# IO.net
KiCad netlist of a schematic drawn in Altium Designer
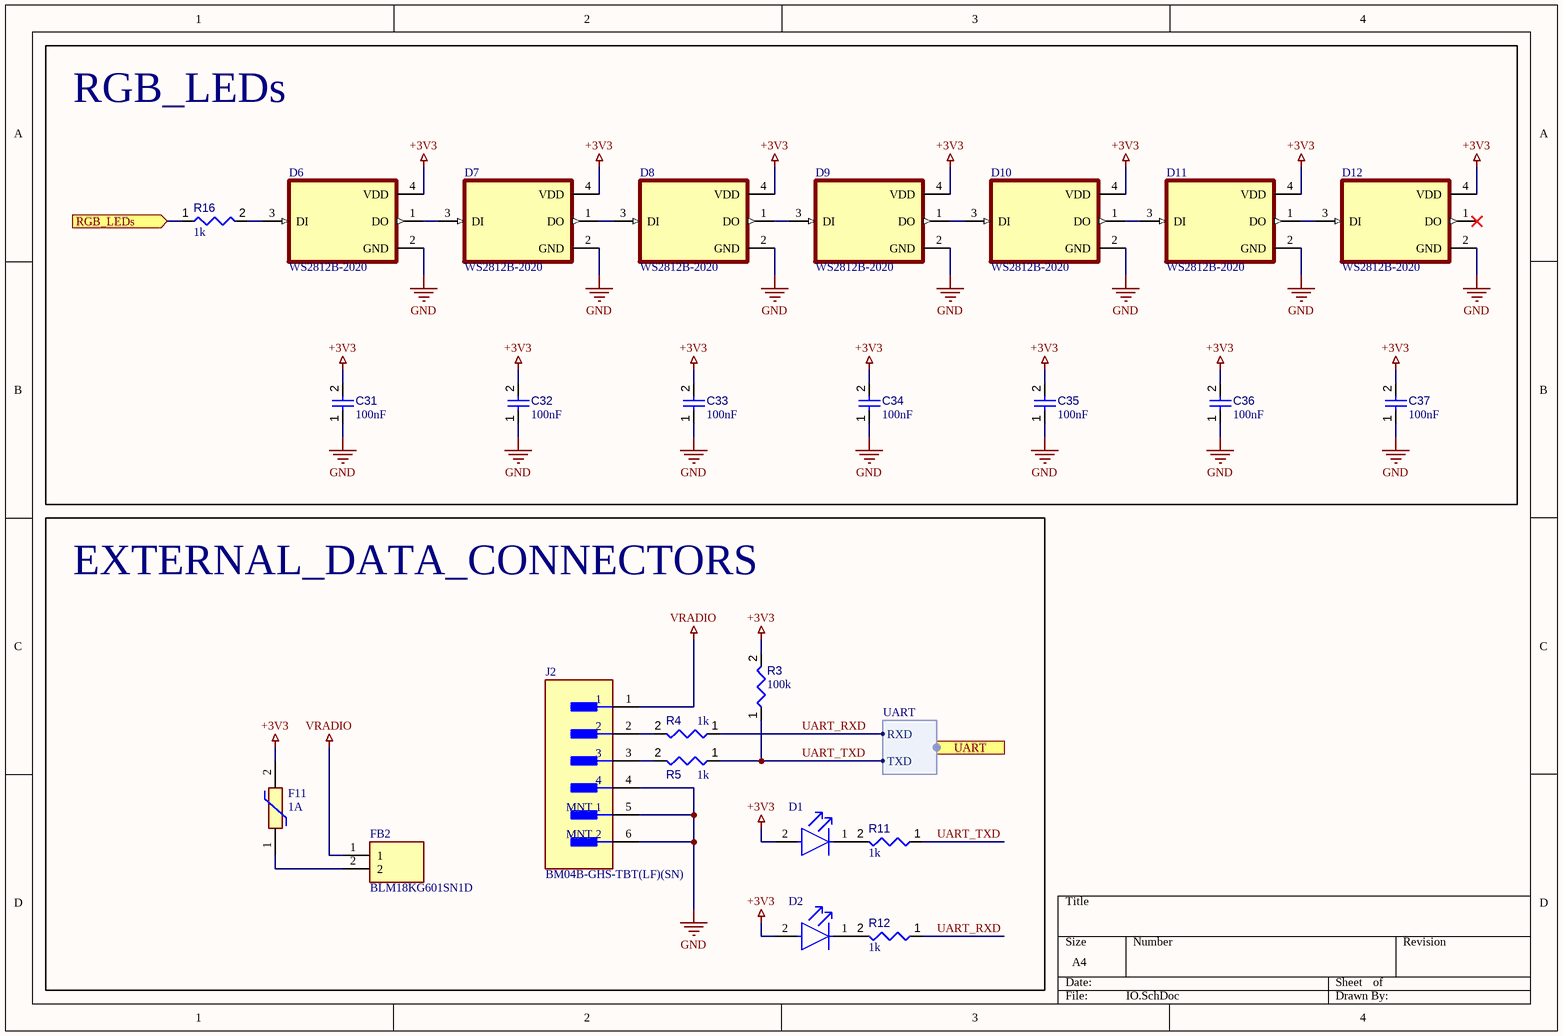
[diagram p0: IO.SchDoc]

(export (version "E")
  (design (tool "Eeschema 10.0.6"))
  (components
    (comp (ref "C31")
      (value "100nF")
      (footprint "CAPC0402(1005)60_L")
      (description "Chip Capacitor, 100nF +/-20%, 10V, 0402, Thickness 0.6 mm")
      (fields (field (name "TOLERANCE") "20%") (field (name "Comment") "Capacitor 100nF +/-20% 10V 0402"))
      (libsource (lib "PWr in Space team") (part "CAP-NP-2"))
    )
    (comp (ref "C32")
      (value "100nF")
      (footprint "CAPC0402(1005)60_L")
      (description "Chip Capacitor, 100nF +/-20%, 10V, 0402, Thickness 0.6 mm")
      (fields (field (name "TOLERANCE") "20%") (field (name "Comment") "Capacitor 100nF +/-20% 10V 0402"))
      (libsource (lib "PWr in Space team") (part "CAP-NP-2"))
    )
    (comp (ref "C33")
      (value "100nF")
      (footprint "CAPC0402(1005)60_L")
      (description "Chip Capacitor, 100nF +/-20%, 10V, 0402, Thickness 0.6 mm")
      (fields (field (name "TOLERANCE") "20%") (field (name "Comment") "Capacitor 100nF +/-20% 10V 0402"))
      (libsource (lib "PWr in Space team") (part "CAP-NP-2"))
    )
    (comp (ref "C34")
      (value "100nF")
      (footprint "CAPC0402(1005)60_L")
      (description "Chip Capacitor, 100nF +/-20%, 10V, 0402, Thickness 0.6 mm")
      (fields (field (name "TOLERANCE") "20%") (field (name "Comment") "Capacitor 100nF +/-20% 10V 0402"))
      (libsource (lib "PWr in Space team") (part "CAP-NP-2"))
    )
    (comp (ref "C35")
      (value "100nF")
      (footprint "CAPC0402(1005)60_L")
      (description "Chip Capacitor, 100nF +/-20%, 10V, 0402, Thickness 0.6 mm")
      (fields (field (name "TOLERANCE") "20%") (field (name "Comment") "Capacitor 100nF +/-20% 10V 0402"))
      (libsource (lib "PWr in Space team") (part "CAP-NP-2"))
    )
    (comp (ref "C36")
      (value "100nF")
      (footprint "CAPC0402(1005)60_L")
      (description "Chip Capacitor, 100nF +/-20%, 10V, 0402, Thickness 0.6 mm")
      (fields (field (name "TOLERANCE") "20%") (field (name "Comment") "Capacitor 100nF +/-20% 10V 0402"))
      (libsource (lib "PWr in Space team") (part "CAP-NP-2"))
    )
    (comp (ref "C37")
      (value "100nF")
      (footprint "CAPC0402(1005)60_L")
      (description "Chip Capacitor, 100nF +/-20%, 10V, 0402, Thickness 0.6 mm")
      (fields (field (name "TOLERANCE") "20%") (field (name "Comment") "Capacitor 100nF +/-20% 10V 0402"))
      (libsource (lib "PWr in Space team") (part "CAP-NP-2"))
    )
    (comp (ref "D1")
      (value "~")
      (footprint "FP-LTST-C191TBKT-MFG")
      (description "LED BLUE CLEAR CHIP SMD")
      (libsource (lib "Altium Content Vault") (part "8706943c75ba83719d021d2fdc84c58"))
    )
    (comp (ref "D2")
      (value "~")
      (footprint "FP-LTST-C191TBKT-MFG")
      (description "LED BLUE CLEAR CHIP SMD")
      (libsource (lib "Altium Content Vault") (part "8706943c75ba83719d021d2fdc84c58"))
    )
    (comp (ref "D6")
      (value "WS2812B-2020")
      (footprint "LED_WS2812-2020")
      (description "Intelligent control LED integrated light source")
      (fields (field (name "MP") "WS2812-2020") (field (name "MF") "{'manufacturer': u'Worldsemi'}"))
      (libsource (lib "SnapEDA_Library") (part "WS2812-2020"))
    )
    (comp (ref "D7")
      (value "WS2812B-2020")
      (footprint "LED_WS2812-2020")
      (description "Intelligent control LED integrated light source")
      (fields (field (name "MP") "WS2812-2020") (field (name "MF") "{'manufacturer': u'Worldsemi'}"))
      (libsource (lib "SnapEDA_Library") (part "WS2812-2020"))
    )
    (comp (ref "D8")
      (value "WS2812B-2020")
      (footprint "LED_WS2812-2020")
      (description "Intelligent control LED integrated light source")
      (fields (field (name "MP") "WS2812-2020") (field (name "MF") "{'manufacturer': u'Worldsemi'}"))
      (libsource (lib "SnapEDA_Library") (part "WS2812-2020"))
    )
    (comp (ref "D9")
      (value "WS2812B-2020")
      (footprint "LED_WS2812-2020")
      (description "Intelligent control LED integrated light source")
      (fields (field (name "MP") "WS2812-2020") (field (name "MF") "{'manufacturer': u'Worldsemi'}"))
      (libsource (lib "SnapEDA_Library") (part "WS2812-2020"))
    )
    (comp (ref "D10")
      (value "WS2812B-2020")
      (footprint "LED_WS2812-2020")
      (description "Intelligent control LED integrated light source")
      (fields (field (name "MP") "WS2812-2020") (field (name "MF") "{'manufacturer': u'Worldsemi'}"))
      (libsource (lib "SnapEDA_Library") (part "WS2812-2020"))
    )
    (comp (ref "D11")
      (value "WS2812B-2020")
      (footprint "LED_WS2812-2020")
      (description "Intelligent control LED integrated light source")
      (fields (field (name "MP") "WS2812-2020") (field (name "MF") "{'manufacturer': u'Worldsemi'}"))
      (libsource (lib "SnapEDA_Library") (part "WS2812-2020"))
    )
    (comp (ref "D12")
      (value "WS2812B-2020")
      (footprint "LED_WS2812-2020")
      (description "Intelligent control LED integrated light source")
      (fields (field (name "MP") "WS2812-2020") (field (name "MF") "{'manufacturer': u'Worldsemi'}"))
      (libsource (lib "SnapEDA_Library") (part "WS2812-2020"))
    )
    (comp (ref "F11")
      (value "1A")
      (footprint "SamacSys:0402L010SLKR")
      (description "Resettable Fuse")
      (fields
        (field (name "MANUFACTURER_PART_NUMBER") "0402L100SLKR")
        (field (name "MOUSER PART NUMBER") "576-0402L100SLKR")
      )
      (libsource (lib "*") (part "0402L100SLKR"))
    )
    (comp (ref "FB2")
      (value "BLM18KG601SN1D")
      (footprint "SamacSys:BLM18EG121SH1D")
      (description "Ferrite Bead")
      (fields (field (name "MOUSER PART NUMBER") "81-BLM18KG601SN1D"))
      (libsource (lib "*") (part "BLM18KG601SN1D"))
    )
    (comp (ref "J2")
      (value "BM04B-GHS-TBT(LF)(SN)")
      (footprint "FP-BM04B-GHS-TBT_LF_SN-MFG")
      (description "CONN HEADER SMD 4POS 1.25MM")
      (libsource (lib "Altium Content Vault") (part "8e3688c4b118bffc0dd9b7401e414ba"))
    )
    (comp (ref "R3")
      (value "100k")
      (footprint "RESC0402(1005)_L")
      (description "Chip Resistor, 100 kOhms, +/-1 %, 63 mW, -55 to 155 degC, 0402")
      (fields (field (name "TOLERANCE") "1%") (field (name "POWER") "63mW"))
      (libsource (lib "PWr in Space team") (part "RES-2"))
    )
    (comp (ref "R4")
      (value "1k")
      (footprint "RESC0402(1005)_L")
      (description "Chip Resistor, 1 kOhms, +/-5 %, 63 mW, -55 to 155 degC, 0402")
      (fields (field (name "TOLERANCE") "5%") (field (name "POWER") "63mW"))
      (libsource (lib "PWr in Space team") (part "RES-2"))
    )
    (comp (ref "R5")
      (value "1k")
      (footprint "RESC0402(1005)_L")
      (description "Chip Resistor, 1 kOhms, +/-5 %, 63 mW, -55 to 155 degC, 0402")
      (fields (field (name "TOLERANCE") "5%") (field (name "POWER") "63mW"))
      (libsource (lib "PWr in Space team") (part "RES-2"))
    )
    (comp (ref "R11")
      (value "1k")
      (footprint "RESC0402(1005)_L")
      (description "Chip Resistor, 1 kOhms, +/-5 %, 63 mW, -55 to 155 degC, 0402")
      (fields (field (name "TOLERANCE") "5%") (field (name "POWER") "63mW"))
      (libsource (lib "PWr in Space team") (part "RES-2"))
    )
    (comp (ref "R12")
      (value "1k")
      (footprint "RESC0402(1005)_L")
      (description "Chip Resistor, 1 kOhms, +/-5 %, 63 mW, -55 to 155 degC, 0402")
      (fields (field (name "TOLERANCE") "5%") (field (name "POWER") "63mW"))
      (libsource (lib "PWr in Space team") (part "RES-2"))
    )
    (comp (ref "R16")
      (value "1k")
      (footprint "RESC0402(1005)_L")
      (description "Chip Resistor, 1 kOhms, +/-5 %, 63 mW, -55 to 155 degC, 0402")
      (fields (field (name "TOLERANCE") "5%") (field (name "POWER") "63mW"))
      (libsource (lib "PWr in Space team") (part "RES-2"))
    )
  )
  (nets
    (net (code "2") (name "+3V3") (class "Default")
      (node (ref "C31") (pin "2") (pinfunction "2_2") (pintype "passive"))
      (node (ref "C32") (pin "2") (pinfunction "2_2") (pintype "passive"))
      (node (ref "C33") (pin "2") (pinfunction "2_2") (pintype "passive"))
      (node (ref "C34") (pin "2") (pinfunction "2_2") (pintype "passive"))
      (node (ref "C35") (pin "2") (pinfunction "2_2") (pintype "passive"))
      (node (ref "C36") (pin "2") (pinfunction "2_2") (pintype "passive"))
      (node (ref "C37") (pin "2") (pinfunction "2_2") (pintype "passive"))
      (node (ref "D1") (pin "2") (pinfunction "A_2") (pintype "passive"))
      (node (ref "D10") (pin "4") (pinfunction "VDD_4") (pintype "power_in"))
      (node (ref "D11") (pin "4") (pinfunction "VDD_4") (pintype "power_in"))
      (node (ref "D12") (pin "4") (pinfunction "VDD_4") (pintype "power_in"))
      (node (ref "D2") (pin "2") (pinfunction "A_2") (pintype "passive"))
      (node (ref "D6") (pin "4") (pinfunction "VDD_4") (pintype "power_in"))
      (node (ref "D7") (pin "4") (pinfunction "VDD_4") (pintype "power_in"))
      (node (ref "D8") (pin "4") (pinfunction "VDD_4") (pintype "power_in"))
      (node (ref "D9") (pin "4") (pinfunction "VDD_4") (pintype "power_in"))
      (node (ref "F11") (pin "2") (pinfunction "2_2") (pintype "passive"))
      (node (ref "R3") (pin "2") (pinfunction "2_2") (pintype "passive"))
    )
    (net (code "3") (name "/RGB_LEDs") (class "Default")
      (node (ref "R16") (pin "1") (pinfunction "1_1") (pintype "passive"))
    )
    (net (code "4") (name "/UART_RXD") (class "Default")
      (node (ref "R12") (pin "1") (pinfunction "1_1") (pintype "passive"))
      (node (ref "R4") (pin "1") (pinfunction "1_1") (pintype "passive"))
    )
    (net (code "5") (name "/UART_TXD") (class "Default")
      (node (ref "R11") (pin "1") (pinfunction "1_1") (pintype "passive"))
      (node (ref "R3") (pin "1") (pinfunction "1_1") (pintype "passive"))
      (node (ref "R5") (pin "1") (pinfunction "1_1") (pintype "passive"))
    )
    (net (code "7") (name "GND") (class "Default")
      (node (ref "C31") (pin "1") (pinfunction "1_1") (pintype "passive"))
      (node (ref "C32") (pin "1") (pinfunction "1_1") (pintype "passive"))
      (node (ref "C33") (pin "1") (pinfunction "1_1") (pintype "passive"))
      (node (ref "C34") (pin "1") (pinfunction "1_1") (pintype "passive"))
      (node (ref "C35") (pin "1") (pinfunction "1_1") (pintype "passive"))
      (node (ref "C36") (pin "1") (pinfunction "1_1") (pintype "passive"))
      (node (ref "C37") (pin "1") (pinfunction "1_1") (pintype "passive"))
      (node (ref "D10") (pin "2") (pinfunction "GND_2") (pintype "power_in"))
      (node (ref "D11") (pin "2") (pinfunction "GND_2") (pintype "power_in"))
      (node (ref "D12") (pin "2") (pinfunction "GND_2") (pintype "power_in"))
      (node (ref "D6") (pin "2") (pinfunction "GND_2") (pintype "power_in"))
      (node (ref "D7") (pin "2") (pinfunction "GND_2") (pintype "power_in"))
      (node (ref "D8") (pin "2") (pinfunction "GND_2") (pintype "power_in"))
      (node (ref "D9") (pin "2") (pinfunction "GND_2") (pintype "power_in"))
      (node (ref "J2") (pin "4") (pinfunction "4_4") (pintype "passive"))
      (node (ref "J2") (pin "5") (pinfunction "MNT_1_5") (pintype "passive"))
      (node (ref "J2") (pin "6") (pinfunction "MNT_2_6") (pintype "passive"))
    )
    (net (code "8") (name "Net-(D1-C)") (class "Default")
      (node (ref "D1") (pin "1") (pinfunction "C_1") (pintype "passive"))
      (node (ref "R11") (pin "2") (pinfunction "2_2") (pintype "passive"))
    )
    (net (code "9") (name "Net-(D2-C)") (class "Default")
      (node (ref "D2") (pin "1") (pinfunction "C_1") (pintype "passive"))
      (node (ref "R12") (pin "2") (pinfunction "2_2") (pintype "passive"))
    )
    (net (code "10") (name "Net-(D6-DI)") (class "Default")
      (node (ref "D6") (pin "3") (pinfunction "DI_3") (pintype "input"))
      (node (ref "R16") (pin "2") (pinfunction "2_2") (pintype "passive"))
    )
    (net (code "11") (name "Net-(D6-DO)") (class "Default")
      (node (ref "D6") (pin "1") (pinfunction "DO_1") (pintype "output"))
      (node (ref "D7") (pin "3") (pinfunction "DI_3") (pintype "input"))
    )
    (net (code "12") (name "Net-(D7-DO)") (class "Default")
      (node (ref "D7") (pin "1") (pinfunction "DO_1") (pintype "output"))
      (node (ref "D8") (pin "3") (pinfunction "DI_3") (pintype "input"))
    )
    (net (code "13") (name "Net-(D8-DO)") (class "Default")
      (node (ref "D8") (pin "1") (pinfunction "DO_1") (pintype "output"))
      (node (ref "D9") (pin "3") (pinfunction "DI_3") (pintype "input"))
    )
    (net (code "14") (name "Net-(D10-DI)") (class "Default")
      (node (ref "D10") (pin "3") (pinfunction "DI_3") (pintype "input"))
      (node (ref "D9") (pin "1") (pinfunction "DO_1") (pintype "output"))
    )
    (net (code "15") (name "Net-(D10-DO)") (class "Default")
      (node (ref "D10") (pin "1") (pinfunction "DO_1") (pintype "output"))
      (node (ref "D11") (pin "3") (pinfunction "DI_3") (pintype "input"))
    )
    (net (code "16") (name "Net-(D11-DO)") (class "Default")
      (node (ref "D11") (pin "1") (pinfunction "DO_1") (pintype "output"))
      (node (ref "D12") (pin "3") (pinfunction "DI_3") (pintype "input"))
    )
    (net (code "17") (name "Net-(F11-Pad1)") (class "Default")
      (node (ref "F11") (pin "1") (pinfunction "1_1") (pintype "passive"))
      (node (ref "FB2") (pin "2") (pinfunction "2_2") (pintype "passive"))
    )
    (net (code "18") (name "Net-(J2-Pad2)") (class "Default")
      (node (ref "J2") (pin "2") (pinfunction "2_2") (pintype "passive"))
      (node (ref "R4") (pin "2") (pinfunction "2_2") (pintype "passive"))
    )
    (net (code "19") (name "Net-(J2-Pad3)") (class "Default")
      (node (ref "J2") (pin "3") (pinfunction "3_3") (pintype "passive"))
      (node (ref "R5") (pin "2") (pinfunction "2_2") (pintype "passive"))
    )
    (net (code "20") (name "VRADIO") (class "Default")
      (node (ref "FB2") (pin "1") (pinfunction "1_1") (pintype "passive"))
      (node (ref "J2") (pin "1") (pinfunction "1_1") (pintype "passive"))
    )
    (net (code "21") (name "unconnected-(D12-DO-Pad1)") (class "Default")
      (node (ref "D12") (pin "1") (pinfunction "DO_1") (pintype "output+no_connect"))
    )
  )
)
